# left_sub.net
KiCad netlist of a schematic drawn in Altium Designer
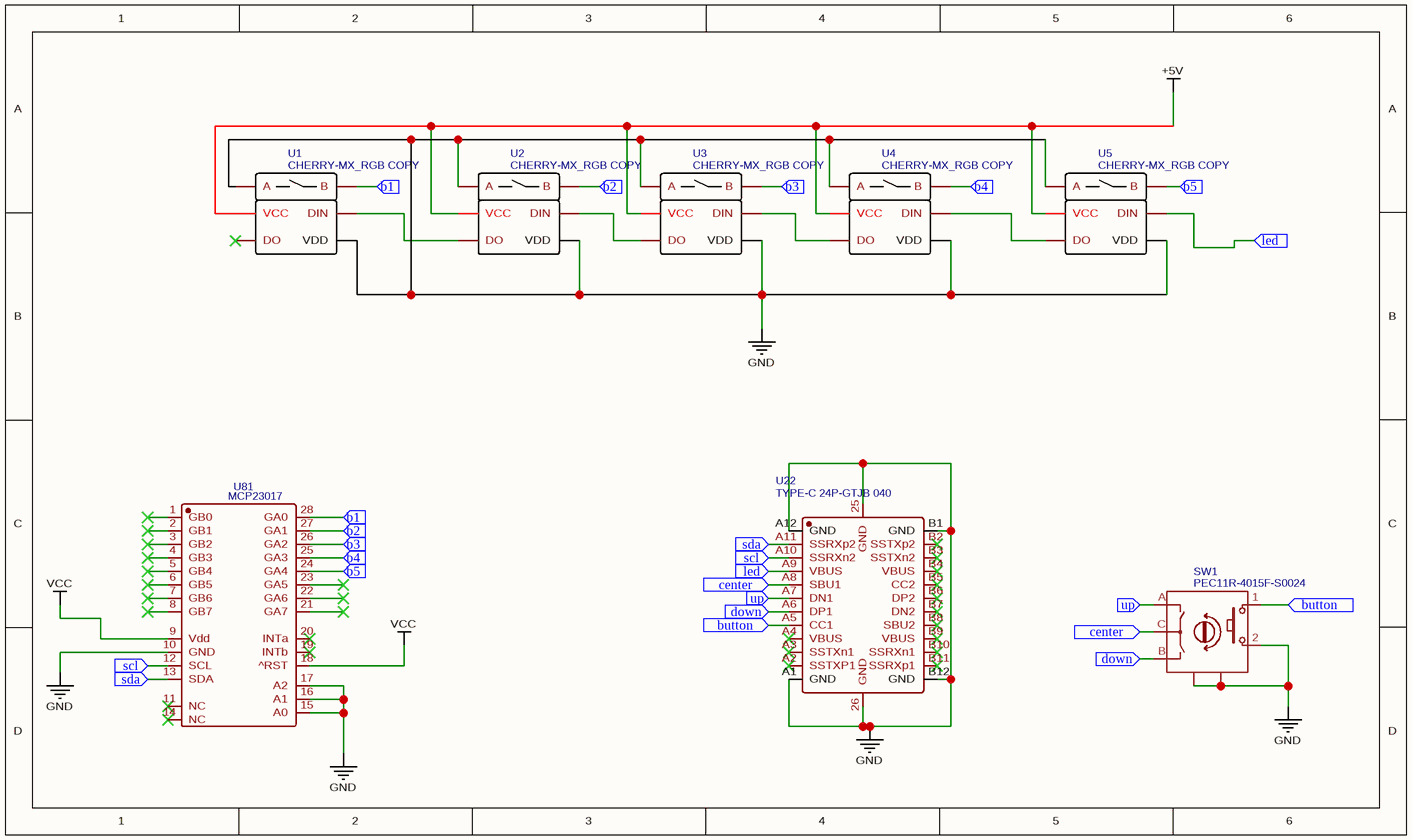
[diagram p0: left sub.schdoc]

(export (version "E")
  (design (tool "Eeschema 10.0.6"))
  (components
    (comp (ref "SW1")
      (value "PEC11R-4015F-S0024")
      (fields (field (name "MANUFACTURER") "BOURNS") (field (name "CONTRIBUTOR") "LCSC"))
      (libsource (lib "altium-import") (part "root_0_PEC11R-4015F-S0024_"))
    )
    (comp (ref "U1")
      (value "CHERRY-MX_RGB COPY")
      (fields (field (name "CONTRIBUTOR") "unrealin01"))
      (libsource (lib "altium-import") (part "root_0_CHERRY-MX_RGB COPY_"))
    )
    (comp (ref "U2")
      (value "CHERRY-MX_RGB COPY")
      (fields (field (name "CONTRIBUTOR") "unrealin01"))
      (libsource (lib "altium-import") (part "root_0_CHERRY-MX_RGB COPY_"))
    )
    (comp (ref "U3")
      (value "CHERRY-MX_RGB COPY")
      (fields (field (name "CONTRIBUTOR") "unrealin01"))
      (libsource (lib "altium-import") (part "root_0_CHERRY-MX_RGB COPY_"))
    )
    (comp (ref "U4")
      (value "CHERRY-MX_RGB COPY")
      (fields (field (name "CONTRIBUTOR") "unrealin01"))
      (libsource (lib "altium-import") (part "root_0_CHERRY-MX_RGB COPY_"))
    )
    (comp (ref "U5")
      (value "CHERRY-MX_RGB COPY")
      (fields (field (name "CONTRIBUTOR") "unrealin01"))
      (libsource (lib "altium-import") (part "root_0_CHERRY-MX_RGB COPY_"))
    )
    (comp (ref "U22")
      (value "TYPE-C 24P-GTJB 040")
      (fields (field (name "MANUFACTURER") "SHOU HAN(首韩)") (field (name "CONTRIBUTOR") "lcsc"))
      (libsource (lib "altium-import") (part "root_0_TYPE-C 24P-GTJB 040_"))
    )
    (comp (ref "U81")
      (value "MCP23017")
      (fields (field (name "CONTRIBUTOR") "tsvstar"))
      (libsource (lib "altium-import") (part "root_0_MCP23017_"))
    )
  )
  (nets
    (net (code "1") (name "+5V") (class "Default")
      (node (ref "U1") (pin "3") (pinfunction "VCC_3") (pintype "passive"))
      (node (ref "U2") (pin "3") (pinfunction "VCC_3") (pintype "passive"))
      (node (ref "U3") (pin "3") (pinfunction "VCC_3") (pintype "passive"))
      (node (ref "U4") (pin "3") (pinfunction "VCC_3") (pintype "passive"))
      (node (ref "U5") (pin "3") (pinfunction "VCC_3") (pintype "passive"))
    )
    (net (code "2") (name "/b1") (class "Default")
      (node (ref "U1") (pin "2") (pinfunction "B_2") (pintype "passive"))
      (node (ref "U81") (pin "28") (pinfunction "GA0_28") (pintype "passive"))
    )
    (net (code "3") (name "/b2") (class "Default")
      (node (ref "U2") (pin "2") (pinfunction "B_2") (pintype "passive"))
      (node (ref "U81") (pin "27") (pinfunction "GA1_27") (pintype "passive"))
    )
    (net (code "4") (name "/b3") (class "Default")
      (node (ref "U3") (pin "2") (pinfunction "B_2") (pintype "passive"))
      (node (ref "U81") (pin "26") (pinfunction "GA2_26") (pintype "passive"))
    )
    (net (code "5") (name "/b4") (class "Default")
      (node (ref "U4") (pin "2") (pinfunction "B_2") (pintype "passive"))
      (node (ref "U81") (pin "25") (pinfunction "GA3_25") (pintype "passive"))
    )
    (net (code "6") (name "/b5") (class "Default")
      (node (ref "U5") (pin "2") (pinfunction "B_2") (pintype "passive"))
      (node (ref "U81") (pin "24") (pinfunction "GA4_24") (pintype "passive"))
    )
    (net (code "7") (name "/button") (class "Default")
      (node (ref "SW1") (pin "1") (pinfunction "1_1") (pintype "passive"))
      (node (ref "U22") (pin "A5") (pinfunction "CC1_A5") (pintype "passive"))
    )
    (net (code "8") (name "/center") (class "Default")
      (node (ref "SW1") (pin "C") (pinfunction "C_C") (pintype "passive"))
      (node (ref "U22") (pin "A8") (pinfunction "SBU1_A8") (pintype "passive"))
    )
    (net (code "9") (name "/down") (class "Default")
      (node (ref "SW1") (pin "B") (pinfunction "B_B") (pintype "passive"))
      (node (ref "U22") (pin "A6") (pinfunction "DP1_A6") (pintype "passive"))
    )
    (net (code "10") (name "/led") (class "Default")
      (node (ref "U22") (pin "A9") (pinfunction "VBUS_A9") (pintype "passive"))
      (node (ref "U5") (pin "6") (pinfunction "DIN_6") (pintype "passive"))
    )
    (net (code "11") (name "/scl") (class "Default")
      (node (ref "U22") (pin "A10") (pinfunction "SSRXn2_A10") (pintype "passive"))
      (node (ref "U81") (pin "12") (pinfunction "SCL_12") (pintype "passive"))
    )
    (net (code "12") (name "/sda") (class "Default")
      (node (ref "U22") (pin "A11") (pinfunction "SSRXp2_A11") (pintype "passive"))
      (node (ref "U81") (pin "13") (pinfunction "SDA_13") (pintype "passive"))
    )
    (net (code "13") (name "/up") (class "Default")
      (node (ref "SW1") (pin "A") (pinfunction "A_A") (pintype "passive"))
      (node (ref "U22") (pin "A7") (pinfunction "DN1_A7") (pintype "passive"))
    )
    (net (code "14") (name "GND") (class "Default")
      (node (ref "SW1") (pin "2") (pinfunction "2_2") (pintype "passive"))
      (node (ref "SW1") (pin "MT1") (pinfunction "MT1_MT1") (pintype "passive"))
      (node (ref "SW1") (pin "MT2") (pinfunction "MT2_MT2") (pintype "passive"))
      (node (ref "U1") (pin "1") (pinfunction "A_1") (pintype "passive"))
      (node (ref "U1") (pin "5") (pinfunction "VDD_5") (pintype "passive"))
      (node (ref "U2") (pin "1") (pinfunction "A_1") (pintype "passive"))
      (node (ref "U2") (pin "5") (pinfunction "VDD_5") (pintype "passive"))
      (node (ref "U22") (pin "25") (pinfunction "GND_25") (pintype "passive"))
      (node (ref "U22") (pin "26") (pinfunction "GND_26") (pintype "passive"))
      (node (ref "U22") (pin "A1") (pinfunction "GND_A1") (pintype "passive"))
      (node (ref "U22") (pin "A12") (pinfunction "GND_A12") (pintype "passive"))
      (node (ref "U22") (pin "B1") (pinfunction "GND_B1") (pintype "passive"))
      (node (ref "U22") (pin "B12") (pinfunction "GND_B12") (pintype "passive"))
      (node (ref "U3") (pin "1") (pinfunction "A_1") (pintype "passive"))
      (node (ref "U3") (pin "5") (pinfunction "VDD_5") (pintype "passive"))
      (node (ref "U4") (pin "1") (pinfunction "A_1") (pintype "passive"))
      (node (ref "U4") (pin "5") (pinfunction "VDD_5") (pintype "passive"))
      (node (ref "U5") (pin "1") (pinfunction "A_1") (pintype "passive"))
      (node (ref "U5") (pin "5") (pinfunction "VDD_5") (pintype "passive"))
      (node (ref "U81") (pin "10") (pinfunction "GND_10") (pintype "passive"))
      (node (ref "U81") (pin "15") (pinfunction "A0_15") (pintype "passive"))
      (node (ref "U81") (pin "16") (pinfunction "A1_16") (pintype "passive"))
      (node (ref "U81") (pin "17") (pinfunction "A2_17") (pintype "passive"))
    )
    (net (code "15") (name "Net-(U1-DIN)") (class "Default")
      (node (ref "U1") (pin "6") (pinfunction "DIN_6") (pintype "passive"))
      (node (ref "U2") (pin "4") (pinfunction "DO_4") (pintype "passive"))
    )
    (net (code "16") (name "Net-(U2-DIN)") (class "Default")
      (node (ref "U2") (pin "6") (pinfunction "DIN_6") (pintype "passive"))
      (node (ref "U3") (pin "4") (pinfunction "DO_4") (pintype "passive"))
    )
    (net (code "17") (name "Net-(U3-DIN)") (class "Default")
      (node (ref "U3") (pin "6") (pinfunction "DIN_6") (pintype "passive"))
      (node (ref "U4") (pin "4") (pinfunction "DO_4") (pintype "passive"))
    )
    (net (code "18") (name "Net-(U4-DIN)") (class "Default")
      (node (ref "U4") (pin "6") (pinfunction "DIN_6") (pintype "passive"))
      (node (ref "U5") (pin "4") (pinfunction "DO_4") (pintype "passive"))
    )
    (net (code "19") (name "VCC") (class "Default")
      (node (ref "U81") (pin "18") (pinfunction "^RST_18") (pintype "passive"))
      (node (ref "U81") (pin "9") (pinfunction "Vdd_9") (pintype "passive"))
    )
    (net (code "20") (name "unconnected-(U1-DO-Pad4)") (class "Default")
      (node (ref "U1") (pin "4") (pinfunction "DO_4") (pintype "passive+no_connect"))
    )
    (net (code "21") (name "unconnected-(U22-CC2-PadB5)") (class "Default")
      (node (ref "U22") (pin "B5") (pinfunction "CC2_B5") (pintype "passive+no_connect"))
    )
    (net (code "22") (name "unconnected-(U22-DN2-PadB7)") (class "Default")
      (node (ref "U22") (pin "B7") (pinfunction "DN2_B7") (pintype "passive+no_connect"))
    )
    (net (code "23") (name "unconnected-(U22-DP2-PadB6)") (class "Default")
      (node (ref "U22") (pin "B6") (pinfunction "DP2_B6") (pintype "passive+no_connect"))
    )
    (net (code "24") (name "unconnected-(U22-SBU2-PadB8)") (class "Default")
      (node (ref "U22") (pin "B8") (pinfunction "SBU2_B8") (pintype "passive+no_connect"))
    )
    (net (code "25") (name "unconnected-(U22-SSRXn1-PadB10)") (class "Default")
      (node (ref "U22") (pin "B10") (pinfunction "SSRXn1_B10") (pintype "passive+no_connect"))
    )
    (net (code "26") (name "unconnected-(U22-SSRXp1-PadB11)") (class "Default")
      (node (ref "U22") (pin "B11") (pinfunction "SSRXp1_B11") (pintype "passive+no_connect"))
    )
    (net (code "27") (name "unconnected-(U22-SSTXP1-PadA2)") (class "Default")
      (node (ref "U22") (pin "A2") (pinfunction "SSTXP1_A2") (pintype "passive+no_connect"))
    )
    (net (code "28") (name "unconnected-(U22-SSTXn1-PadA3)") (class "Default")
      (node (ref "U22") (pin "A3") (pinfunction "SSTXn1_A3") (pintype "passive+no_connect"))
    )
    (net (code "29") (name "unconnected-(U22-SSTXn2-PadB3)") (class "Default")
      (node (ref "U22") (pin "B3") (pinfunction "SSTXn2_B3") (pintype "passive+no_connect"))
    )
    (net (code "30") (name "unconnected-(U22-SSTXp2-PadB2)") (class "Default")
      (node (ref "U22") (pin "B2") (pinfunction "SSTXp2_B2") (pintype "passive+no_connect"))
    )
    (net (code "31") (name "unconnected-(U22-VBUS-PadA4)") (class "Default")
      (node (ref "U22") (pin "A4") (pinfunction "VBUS_A4") (pintype "passive+no_connect"))
    )
    (net (code "32") (name "unconnected-(U22-VBUS-PadB4)") (class "Default")
      (node (ref "U22") (pin "B4") (pinfunction "VBUS_B4") (pintype "passive+no_connect"))
    )
    (net (code "33") (name "unconnected-(U22-VBUS-PadB9)") (class "Default")
      (node (ref "U22") (pin "B9") (pinfunction "VBUS_B9") (pintype "passive+no_connect"))
    )
    (net (code "34") (name "unconnected-(U81-GA5-Pad23)") (class "Default")
      (node (ref "U81") (pin "23") (pinfunction "GA5_23") (pintype "passive+no_connect"))
    )
    (net (code "35") (name "unconnected-(U81-GA6-Pad22)") (class "Default")
      (node (ref "U81") (pin "22") (pinfunction "GA6_22") (pintype "passive+no_connect"))
    )
    (net (code "36") (name "unconnected-(U81-GA7-Pad21)") (class "Default")
      (node (ref "U81") (pin "21") (pinfunction "GA7_21") (pintype "passive+no_connect"))
    )
    (net (code "37") (name "unconnected-(U81-GB0-Pad1)") (class "Default")
      (node (ref "U81") (pin "1") (pinfunction "GB0_1") (pintype "passive+no_connect"))
    )
    (net (code "38") (name "unconnected-(U81-GB1-Pad2)") (class "Default")
      (node (ref "U81") (pin "2") (pinfunction "GB1_2") (pintype "passive+no_connect"))
    )
    (net (code "39") (name "unconnected-(U81-GB2-Pad3)") (class "Default")
      (node (ref "U81") (pin "3") (pinfunction "GB2_3") (pintype "passive+no_connect"))
    )
    (net (code "40") (name "unconnected-(U81-GB3-Pad4)") (class "Default")
      (node (ref "U81") (pin "4") (pinfunction "GB3_4") (pintype "passive+no_connect"))
    )
    (net (code "41") (name "unconnected-(U81-GB4-Pad5)") (class "Default")
      (node (ref "U81") (pin "5") (pinfunction "GB4_5") (pintype "passive+no_connect"))
    )
    (net (code "42") (name "unconnected-(U81-GB5-Pad6)") (class "Default")
      (node (ref "U81") (pin "6") (pinfunction "GB5_6") (pintype "passive+no_connect"))
    )
    (net (code "43") (name "unconnected-(U81-GB6-Pad7)") (class "Default")
      (node (ref "U81") (pin "7") (pinfunction "GB6_7") (pintype "passive+no_connect"))
    )
    (net (code "44") (name "unconnected-(U81-GB7-Pad8)") (class "Default")
      (node (ref "U81") (pin "8") (pinfunction "GB7_8") (pintype "passive+no_connect"))
    )
    (net (code "45") (name "unconnected-(U81-INTa-Pad20)") (class "Default")
      (node (ref "U81") (pin "20") (pinfunction "INTa_20") (pintype "passive+no_connect"))
    )
    (net (code "46") (name "unconnected-(U81-INTb-Pad19)") (class "Default")
      (node (ref "U81") (pin "19") (pinfunction "INTb_19") (pintype "passive+no_connect"))
    )
    (net (code "47") (name "unconnected-(U81-NC-Pad11)") (class "Default")
      (node (ref "U81") (pin "11") (pinfunction "NC_11") (pintype "passive+no_connect"))
    )
    (net (code "48") (name "unconnected-(U81-NC-Pad14)") (class "Default")
      (node (ref "U81") (pin "14") (pinfunction "NC_14") (pintype "passive+no_connect"))
    )
  )
)
